# rako-bridge.net
KiCad netlist of a schematic drawn in EAGLE
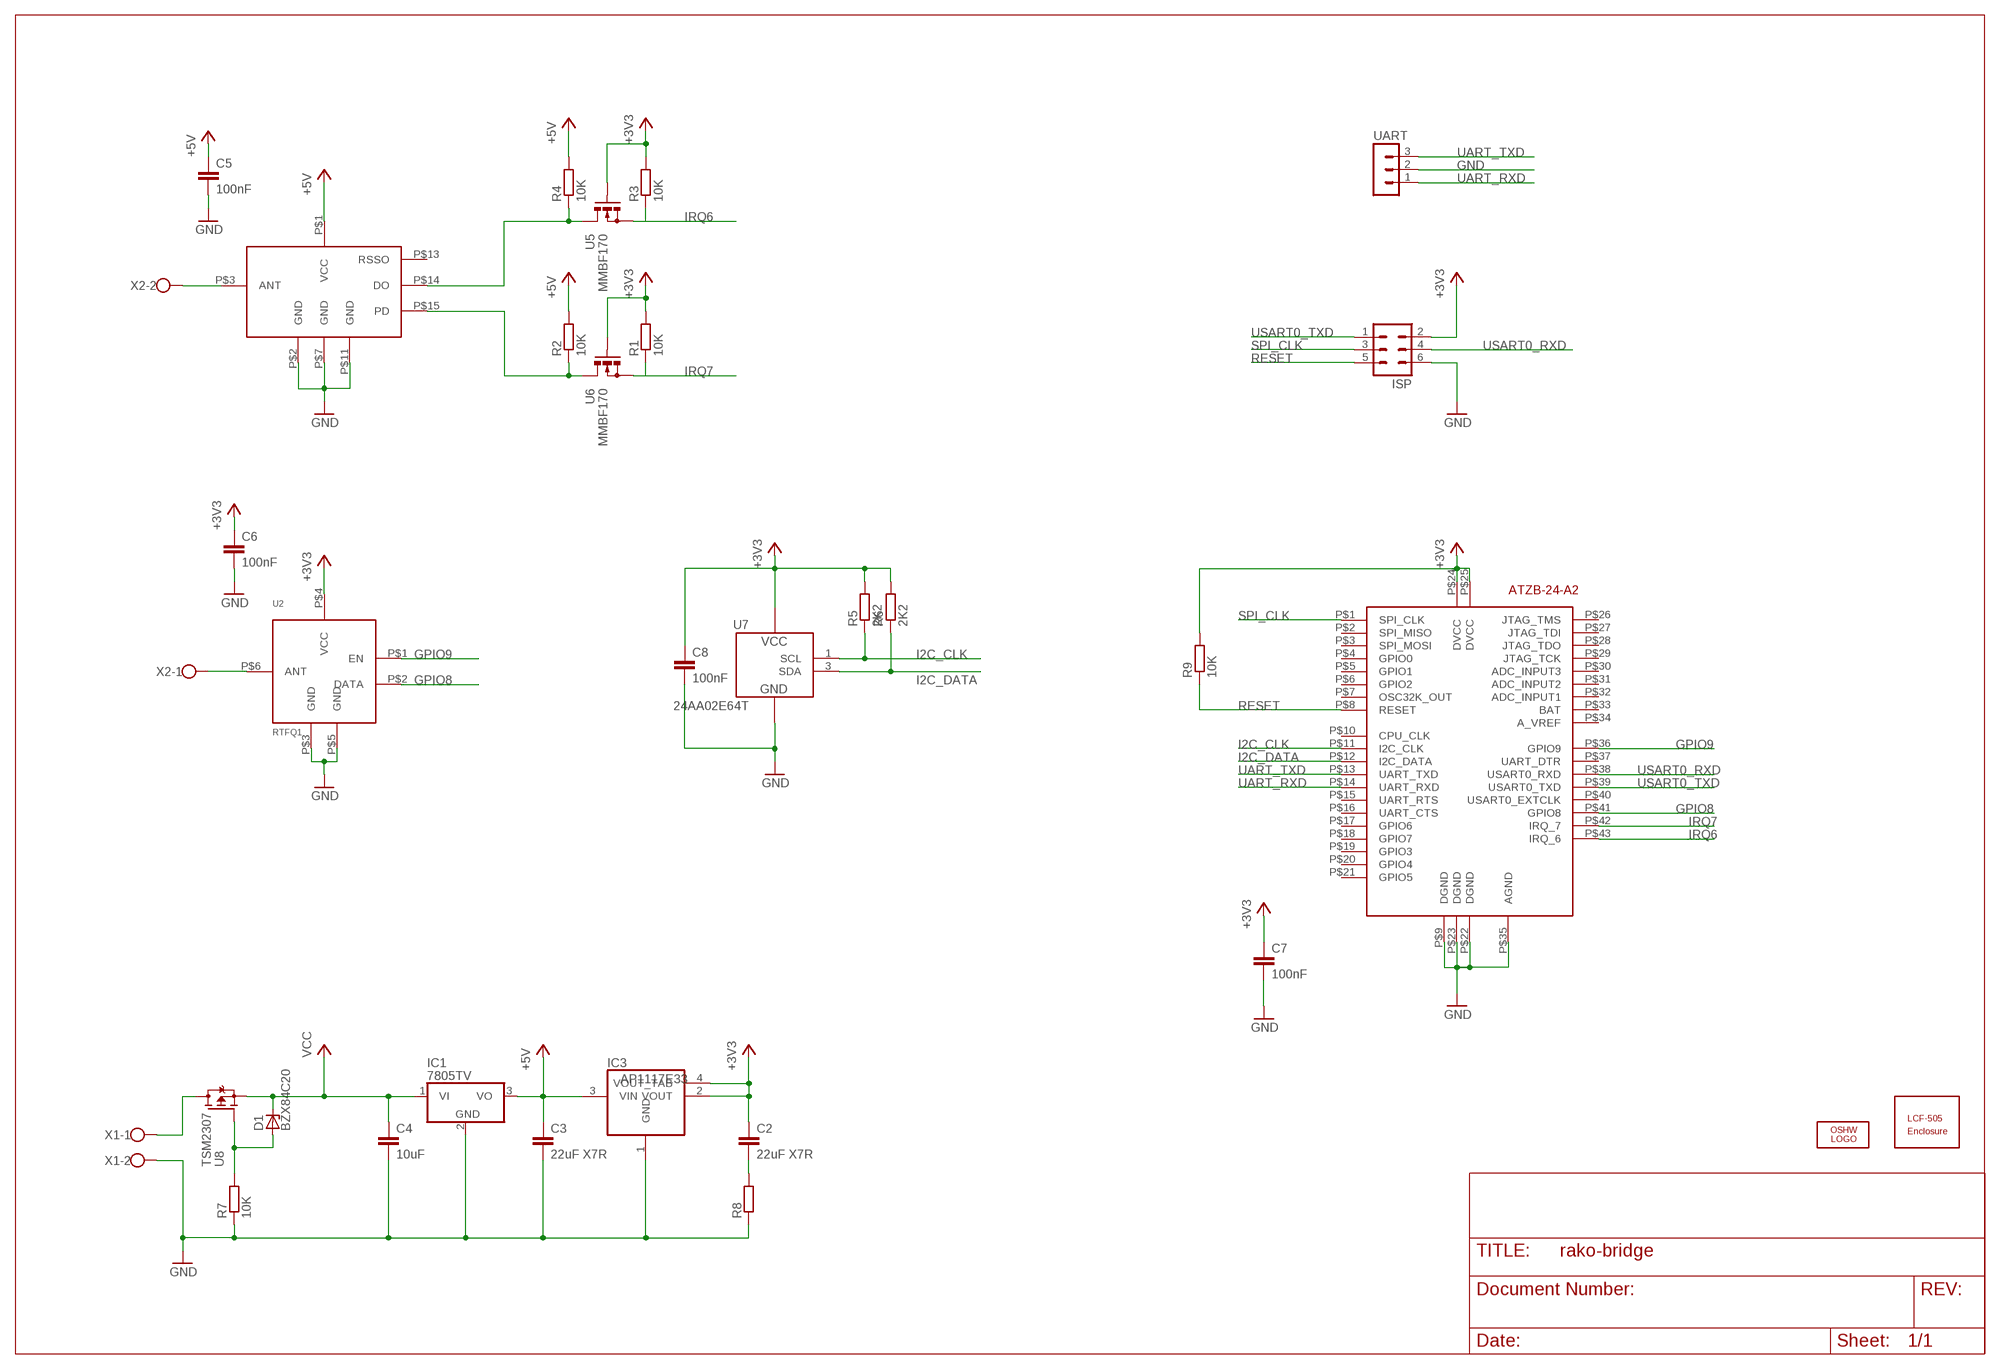
[diagram p0: schematic, sheet 1]

(export (version "E")
  (design (tool "Eeschema 10.0.6"))
  (components
    (comp (ref "C2")
      (value "22uF X7R")
      (footprint "eagle-import:C1210")
      (libsource (lib "eagle-import") (part "C-EUC1210"))
    )
    (comp (ref "C3")
      (value "22uF X7R")
      (footprint "eagle-import:C1210")
      (libsource (lib "eagle-import") (part "C-EUC1210"))
    )
    (comp (ref "C4")
      (value "10uF")
      (footprint "eagle-import:C1210")
      (libsource (lib "eagle-import") (part "C-EUC1210"))
    )
    (comp (ref "C5")
      (value "100nF")
      (footprint "eagle-import:C0603")
      (libsource (lib "eagle-import") (part "C-EUC0603"))
    )
    (comp (ref "C6")
      (value "100nF")
      (footprint "eagle-import:C0603")
      (libsource (lib "eagle-import") (part "C-EUC0603"))
    )
    (comp (ref "C7")
      (value "100nF")
      (footprint "eagle-import:C0603")
      (libsource (lib "eagle-import") (part "C-EUC0603"))
    )
    (comp (ref "C8")
      (value "100nF")
      (footprint "eagle-import:C0603")
      (libsource (lib "eagle-import") (part "C-EUC0603"))
    )
    (comp (ref "D1")
      (value "BZX84C20")
      (footprint "eagle-import:SOT23")
      (libsource (lib "eagle-import") (part "BZX84C"))
    )
    (comp (ref "IC1")
      (value "7805TV")
      (footprint "eagle-import:TO220V")
      (libsource (lib "eagle-import") (part "78TV05"))
    )
    (comp (ref "IC3")
      (value "AP1117E33")
      (footprint "eagle-import:SOT223")
      (fields (field (name "MPN") "REG1117"))
      (libsource (lib "eagle-import") (part "REG1117"))
    )
    (comp (ref "ISP")
      (value "MA03-2")
      (footprint "eagle-import:MA03-2")
      (libsource (lib "eagle-import") (part "MA03-2"))
    )
    (comp (ref "LOGO1")
      (value "OSHW_LOGO_FILLX0200-NT")
      (footprint "eagle-import:OSHW_FILLX200_NOTEXT")
      (libsource (lib "eagle-import") (part "OSHW_LOGO_FILLX0200-NT"))
    )
    (comp (ref "R1")
      (value "10K")
      (footprint "eagle-import:R0603")
      (libsource (lib "eagle-import") (part "R-EU_R0603"))
    )
    (comp (ref "R2")
      (value "10K")
      (footprint "eagle-import:R0603")
      (libsource (lib "eagle-import") (part "R-EU_R0603"))
    )
    (comp (ref "R3")
      (value "10K")
      (footprint "eagle-import:R0603")
      (libsource (lib "eagle-import") (part "R-EU_R0603"))
    )
    (comp (ref "R4")
      (value "10K")
      (footprint "eagle-import:R0603")
      (libsource (lib "eagle-import") (part "R-EU_R0603"))
    )
    (comp (ref "R5")
      (value "2K2")
      (footprint "eagle-import:R0603")
      (libsource (lib "eagle-import") (part "R-EU_R0603"))
    )
    (comp (ref "R6")
      (value "2K2")
      (footprint "eagle-import:R0603")
      (libsource (lib "eagle-import") (part "R-EU_R0603"))
    )
    (comp (ref "R7")
      (value "10K")
      (footprint "eagle-import:R0603")
      (libsource (lib "eagle-import") (part "R-EU_R0603"))
    )
    (comp (ref "R8")
      (value "R-EU_R0603")
      (footprint "eagle-import:R0603")
      (libsource (lib "eagle-import") (part "R-EU_R0603"))
    )
    (comp (ref "R9")
      (value "10K")
      (footprint "eagle-import:R0603")
      (libsource (lib "eagle-import") (part "R-EU_R0603"))
    )
    (comp (ref "U$1")
      (value "BOX-LCF-505")
      (footprint "eagle-import:BOX-LCF-505")
      (libsource (lib "eagle-import") (part "BOX-LCF-505"))
    )
    (comp (ref "U$3")
      (value "ATZB-24-A2")
      (footprint "eagle-import:ATZB-24-A2")
      (libsource (lib "eagle-import") (part "ATZB-24-A2"))
    )
    (comp (ref "U2")
      (value "RTFQ1")
      (footprint "eagle-import:RTFQ1")
      (libsource (lib "eagle-import") (part "RTFQ1"))
    )
    (comp (ref "U4")
      (value "RRFQ1")
      (footprint "eagle-import:RRFQ1")
      (libsource (lib "eagle-import") (part "RRFQ1"))
    )
    (comp (ref "U5")
      (value "MMBF170")
      (footprint "eagle-import:SOT23")
      (libsource (lib "eagle-import") (part "MMBF170"))
    )
    (comp (ref "U6")
      (value "MMBF170")
      (footprint "eagle-import:SOT23")
      (libsource (lib "eagle-import") (part "MMBF170"))
    )
    (comp (ref "U7")
      (value "24AA02E64T")
      (footprint "eagle-import:SOT23-5L")
      (libsource (lib "eagle-import") (part "24AA02E64T"))
    )
    (comp (ref "U8")
      (value "TSM2307")
      (footprint "eagle-import:SOT23")
      (libsource (lib "eagle-import") (part "TSM2307"))
    )
    (comp (ref "UART")
      (value "MA03-1")
      (footprint "eagle-import:MA03-1")
      (libsource (lib "eagle-import") (part "MA03-1"))
    )
    (comp (ref "X1")
      (value "W237-102")
      (footprint "eagle-import:W237-102")
      (fields (field (name "MPN") "237-102"))
      (libsource (lib "eagle-import") (part "W237-102"))
    )
    (comp (ref "X2")
      (value "W237-102")
      (footprint "eagle-import:W237-102")
      (fields (field (name "MPN") "237-102"))
      (libsource (lib "eagle-import") (part "W237-102"))
    )
  )
  (nets
    (net (code "1") (name "+3V3") (class "Default")
      (node (ref "C2") (pin "1") (pinfunction "1_1") (pintype "passive"))
      (node (ref "C6") (pin "1") (pinfunction "1_1") (pintype "passive"))
      (node (ref "C7") (pin "1") (pinfunction "1_1") (pintype "passive"))
      (node (ref "C8") (pin "1") (pinfunction "1_1") (pintype "passive"))
      (node (ref "IC3") (pin "2") (pinfunction "VOUT_2") (pintype "output"))
      (node (ref "IC3") (pin "4") (pinfunction "VOUT_TAB_4") (pintype "output"))
      (node (ref "ISP") (pin "2") (pinfunction "2_2") (pintype "passive"))
      (node (ref "R1") (pin "2") (pinfunction "2_2") (pintype "passive"))
      (node (ref "R3") (pin "2") (pinfunction "2_2") (pintype "passive"))
      (node (ref "R5") (pin "2") (pinfunction "2_2") (pintype "passive"))
      (node (ref "R6") (pin "2") (pinfunction "2_2") (pintype "passive"))
      (node (ref "R9") (pin "2") (pinfunction "2_2") (pintype "passive"))
      (node (ref "U$3") (pin "P$24") (pinfunction "DVCC_P$24") (pintype "bidirectional"))
      (node (ref "U$3") (pin "P$25") (pinfunction "DVCC_P$25") (pintype "bidirectional"))
      (node (ref "U2") (pin "P$4") (pinfunction "VCC_P$4") (pintype "bidirectional"))
      (node (ref "U5") (pin "1") (pinfunction "G_1") (pintype "passive"))
      (node (ref "U6") (pin "1") (pinfunction "G_1") (pintype "passive"))
      (node (ref "U7") (pin "4") (pinfunction "VCC_4") (pintype "bidirectional"))
    )
    (net (code "2") (name "+5V") (class "Default")
      (node (ref "C3") (pin "1") (pinfunction "1_1") (pintype "passive"))
      (node (ref "C5") (pin "1") (pinfunction "1_1") (pintype "passive"))
      (node (ref "IC1") (pin "3") (pinfunction "VO_3") (pintype "passive"))
      (node (ref "IC3") (pin "3") (pinfunction "VIN_3") (pintype "input"))
      (node (ref "R2") (pin "2") (pinfunction "2_2") (pintype "passive"))
      (node (ref "R4") (pin "2") (pinfunction "2_2") (pintype "passive"))
      (node (ref "U4") (pin "P$1") (pinfunction "VCC_P$1") (pintype "bidirectional"))
    )
    (net (code "3") (name "/GPIO8") (class "Default")
      (node (ref "U$3") (pin "P$41") (pinfunction "GPIO8_P$41") (pintype "bidirectional"))
      (node (ref "U2") (pin "P$2") (pinfunction "DATA_P$2") (pintype "bidirectional"))
    )
    (net (code "4") (name "/GPIO9") (class "Default")
      (node (ref "U$3") (pin "P$36") (pinfunction "GPIO9_P$36") (pintype "bidirectional"))
      (node (ref "U2") (pin "P$1") (pinfunction "EN_P$1") (pintype "bidirectional"))
    )
    (net (code "5") (name "/I2C_CLK") (class "Default")
      (node (ref "R5") (pin "1") (pinfunction "1_1") (pintype "passive"))
      (node (ref "U$3") (pin "P$11") (pinfunction "I2C_CLK_P$11") (pintype "bidirectional"))
      (node (ref "U7") (pin "1") (pinfunction "SCL_1") (pintype "bidirectional"))
    )
    (net (code "6") (name "/I2C_DATA") (class "Default")
      (node (ref "R6") (pin "1") (pinfunction "1_1") (pintype "passive"))
      (node (ref "U$3") (pin "P$12") (pinfunction "I2C_DATA_P$12") (pintype "bidirectional"))
      (node (ref "U7") (pin "3") (pinfunction "SDA_3") (pintype "bidirectional"))
    )
    (net (code "7") (name "/IRQ6") (class "Default")
      (node (ref "R3") (pin "1") (pinfunction "1_1") (pintype "passive"))
      (node (ref "U$3") (pin "P$43") (pinfunction "IRQ_6_P$43") (pintype "bidirectional"))
      (node (ref "U5") (pin "2") (pinfunction "S_2") (pintype "passive"))
    )
    (net (code "8") (name "/IRQ7") (class "Default")
      (node (ref "R1") (pin "1") (pinfunction "1_1") (pintype "passive"))
      (node (ref "U$3") (pin "P$42") (pinfunction "IRQ_7_P$42") (pintype "bidirectional"))
      (node (ref "U6") (pin "2") (pinfunction "S_2") (pintype "passive"))
    )
    (net (code "9") (name "/RESET") (class "Default")
      (node (ref "ISP") (pin "5") (pinfunction "5_5") (pintype "passive"))
      (node (ref "R9") (pin "1") (pinfunction "1_1") (pintype "passive"))
      (node (ref "U$3") (pin "P$8") (pinfunction "RESET_P$8") (pintype "bidirectional"))
    )
    (net (code "10") (name "/SPI_CLK") (class "Default")
      (node (ref "ISP") (pin "3") (pinfunction "3_3") (pintype "passive"))
      (node (ref "U$3") (pin "P$1") (pinfunction "SPI_CLK_P$1") (pintype "bidirectional"))
    )
    (net (code "11") (name "/UART_RXD") (class "Default")
      (node (ref "U$3") (pin "P$14") (pinfunction "UART_RXD_P$14") (pintype "bidirectional"))
      (node (ref "UART") (pin "1") (pinfunction "1_1") (pintype "passive"))
    )
    (net (code "12") (name "/UART_TXD") (class "Default")
      (node (ref "U$3") (pin "P$13") (pinfunction "UART_TXD_P$13") (pintype "bidirectional"))
      (node (ref "UART") (pin "3") (pinfunction "3_3") (pintype "passive"))
    )
    (net (code "13") (name "/USART0_RXD") (class "Default")
      (node (ref "ISP") (pin "4") (pinfunction "4_4") (pintype "passive"))
      (node (ref "U$3") (pin "P$38") (pinfunction "USART0_RXD_P$38") (pintype "bidirectional"))
    )
    (net (code "14") (name "/USART0_TXD") (class "Default")
      (node (ref "ISP") (pin "1") (pinfunction "1_1") (pintype "passive"))
      (node (ref "U$3") (pin "P$39") (pinfunction "USART0_TXD_P$39") (pintype "bidirectional"))
    )
    (net (code "15") (name "GND") (class "Default")
      (node (ref "C3") (pin "2") (pinfunction "2_2") (pintype "passive"))
      (node (ref "C4") (pin "2") (pinfunction "2_2") (pintype "passive"))
      (node (ref "C5") (pin "2") (pinfunction "2_2") (pintype "passive"))
      (node (ref "C6") (pin "2") (pinfunction "2_2") (pintype "passive"))
      (node (ref "C7") (pin "2") (pinfunction "2_2") (pintype "passive"))
      (node (ref "C8") (pin "2") (pinfunction "2_2") (pintype "passive"))
      (node (ref "IC1") (pin "2") (pinfunction "GND_2") (pintype "passive"))
      (node (ref "IC3") (pin "1") (pinfunction "GND_1") (pintype "power_in"))
      (node (ref "ISP") (pin "6") (pinfunction "6_6") (pintype "passive"))
      (node (ref "R7") (pin "1") (pinfunction "1_1") (pintype "passive"))
      (node (ref "R8") (pin "1") (pinfunction "1_1") (pintype "passive"))
      (node (ref "U$3") (pin "P$22") (pinfunction "DGND_P$22") (pintype "bidirectional"))
      (node (ref "U$3") (pin "P$23") (pinfunction "DGND_P$23") (pintype "bidirectional"))
      (node (ref "U$3") (pin "P$35") (pinfunction "AGND_P$35") (pintype "bidirectional"))
      (node (ref "U$3") (pin "P$9") (pinfunction "DGND_P$9") (pintype "bidirectional"))
      (node (ref "U2") (pin "P$3") (pinfunction "GND_P$3") (pintype "bidirectional"))
      (node (ref "U2") (pin "P$5") (pinfunction "GND_P$5") (pintype "bidirectional"))
      (node (ref "U4") (pin "P$11") (pinfunction "GND_P$11") (pintype "bidirectional"))
      (node (ref "U4") (pin "P$2") (pinfunction "GND_P$2") (pintype "bidirectional"))
      (node (ref "U4") (pin "P$7") (pinfunction "GND_P$7") (pintype "bidirectional"))
      (node (ref "U7") (pin "2") (pinfunction "VSS_2") (pintype "bidirectional"))
      (node (ref "UART") (pin "2") (pinfunction "2_2") (pintype "passive"))
      (node (ref "X1") (pin "2") (pinfunction "KL_2") (pintype "passive"))
    )
    (net (code "16") (name "Net-(C2-Pad2)") (class "Default")
      (node (ref "C2") (pin "2") (pinfunction "2_2") (pintype "passive"))
      (node (ref "R8") (pin "2") (pinfunction "2_2") (pintype "passive"))
    )
    (net (code "17") (name "Net-(D1-A)") (class "Default")
      (node (ref "D1") (pin "1") (pinfunction "A_1") (pintype "passive"))
      (node (ref "R7") (pin "2") (pinfunction "2_2") (pintype "passive"))
      (node (ref "U8") (pin "1") (pinfunction "G_1") (pintype "passive"))
    )
    (net (code "18") (name "Net-(U2-ANT)") (class "Default")
      (node (ref "U2") (pin "P$6") (pinfunction "ANT_P$6") (pintype "bidirectional"))
      (node (ref "X2") (pin "1") (pinfunction "KL_1") (pintype "passive"))
    )
    (net (code "19") (name "Net-(U4-ANT)") (class "Default")
      (node (ref "U4") (pin "P$3") (pinfunction "ANT_P$3") (pintype "bidirectional"))
      (node (ref "X2") (pin "2") (pinfunction "KL_2") (pintype "passive"))
    )
    (net (code "20") (name "Net-(U4-DO)") (class "Default")
      (node (ref "R4") (pin "1") (pinfunction "1_1") (pintype "passive"))
      (node (ref "U4") (pin "P$14") (pinfunction "DO_P$14") (pintype "bidirectional"))
      (node (ref "U5") (pin "3") (pinfunction "D_3") (pintype "passive"))
    )
    (net (code "21") (name "Net-(U4-PD)") (class "Default")
      (node (ref "R2") (pin "1") (pinfunction "1_1") (pintype "passive"))
      (node (ref "U4") (pin "P$15") (pinfunction "PD_P$15") (pintype "bidirectional"))
      (node (ref "U6") (pin "3") (pinfunction "D_3") (pintype "passive"))
    )
    (net (code "22") (name "Net-(U8-D)") (class "Default")
      (node (ref "U8") (pin "3") (pinfunction "D_3") (pintype "passive"))
      (node (ref "X1") (pin "1") (pinfunction "KL_1") (pintype "passive"))
    )
    (net (code "23") (name "VCC") (class "Default")
      (node (ref "C4") (pin "1") (pinfunction "1_1") (pintype "passive"))
      (node (ref "D1") (pin "3") (pinfunction "C_3") (pintype "passive"))
      (node (ref "IC1") (pin "1") (pinfunction "VI_1") (pintype "input"))
      (node (ref "U8") (pin "2") (pinfunction "S_2") (pintype "passive"))
    )
    (net (code "24") (name "unconnected-(U$3-ADC_INPUT1-PadP$32)") (class "Default")
      (node (ref "U$3") (pin "P$32") (pinfunction "ADC_INPUT1_P$32") (pintype "bidirectional"))
    )
    (net (code "25") (name "unconnected-(U$3-ADC_INPUT2-PadP$31)") (class "Default")
      (node (ref "U$3") (pin "P$31") (pinfunction "ADC_INPUT2_P$31") (pintype "bidirectional"))
    )
    (net (code "26") (name "unconnected-(U$3-ADC_INPUT3-PadP$30)") (class "Default")
      (node (ref "U$3") (pin "P$30") (pinfunction "ADC_INPUT3_P$30") (pintype "bidirectional"))
    )
    (net (code "27") (name "unconnected-(U$3-A_VREF-PadP$34)") (class "Default")
      (node (ref "U$3") (pin "P$34") (pinfunction "A_VREF_P$34") (pintype "bidirectional"))
    )
    (net (code "28") (name "unconnected-(U$3-BAT-PadP$33)") (class "Default")
      (node (ref "U$3") (pin "P$33") (pinfunction "BAT_P$33") (pintype "bidirectional"))
    )
    (net (code "29") (name "unconnected-(U$3-CPU_CLK-PadP$10)") (class "Default")
      (node (ref "U$3") (pin "P$10") (pinfunction "CPU_CLK_P$10") (pintype "bidirectional"))
    )
    (net (code "30") (name "unconnected-(U$3-GPIO0-PadP$4)") (class "Default")
      (node (ref "U$3") (pin "P$4") (pinfunction "GPIO0_P$4") (pintype "bidirectional"))
    )
    (net (code "31") (name "unconnected-(U$3-GPIO1-PadP$5)") (class "Default")
      (node (ref "U$3") (pin "P$5") (pinfunction "GPIO1_P$5") (pintype "bidirectional"))
    )
    (net (code "32") (name "unconnected-(U$3-GPIO2-PadP$6)") (class "Default")
      (node (ref "U$3") (pin "P$6") (pinfunction "GPIO2_P$6") (pintype "bidirectional"))
    )
    (net (code "33") (name "unconnected-(U$3-GPIO3-PadP$19)") (class "Default")
      (node (ref "U$3") (pin "P$19") (pinfunction "GPIO3_P$19") (pintype "bidirectional"))
    )
    (net (code "34") (name "unconnected-(U$3-GPIO4-PadP$20)") (class "Default")
      (node (ref "U$3") (pin "P$20") (pinfunction "GPIO4_P$20") (pintype "bidirectional"))
    )
    (net (code "35") (name "unconnected-(U$3-GPIO5-PadP$21)") (class "Default")
      (node (ref "U$3") (pin "P$21") (pinfunction "GPIO5_P$21") (pintype "bidirectional"))
    )
    (net (code "36") (name "unconnected-(U$3-GPIO6-PadP$17)") (class "Default")
      (node (ref "U$3") (pin "P$17") (pinfunction "GPIO6_P$17") (pintype "bidirectional"))
    )
    (net (code "37") (name "unconnected-(U$3-GPIO7-PadP$18)") (class "Default")
      (node (ref "U$3") (pin "P$18") (pinfunction "GPIO7_P$18") (pintype "bidirectional"))
    )
    (net (code "38") (name "unconnected-(U$3-JTAG_TCK-PadP$29)") (class "Default")
      (node (ref "U$3") (pin "P$29") (pinfunction "JTAG_TCK_P$29") (pintype "bidirectional"))
    )
    (net (code "39") (name "unconnected-(U$3-JTAG_TDI-PadP$27)") (class "Default")
      (node (ref "U$3") (pin "P$27") (pinfunction "JTAG_TDI_P$27") (pintype "bidirectional"))
    )
    (net (code "40") (name "unconnected-(U$3-JTAG_TDO-PadP$28)") (class "Default")
      (node (ref "U$3") (pin "P$28") (pinfunction "JTAG_TDO_P$28") (pintype "bidirectional"))
    )
    (net (code "41") (name "unconnected-(U$3-JTAG_TMS-PadP$26)") (class "Default")
      (node (ref "U$3") (pin "P$26") (pinfunction "JTAG_TMS_P$26") (pintype "bidirectional"))
    )
    (net (code "42") (name "unconnected-(U$3-OSC32K_OUT-PadP$7)") (class "Default")
      (node (ref "U$3") (pin "P$7") (pinfunction "OSC32K_OUT_P$7") (pintype "bidirectional"))
    )
    (net (code "43") (name "unconnected-(U$3-SPI_MISO-PadP$2)") (class "Default")
      (node (ref "U$3") (pin "P$2") (pinfunction "SPI_MISO_P$2") (pintype "bidirectional"))
    )
    (net (code "44") (name "unconnected-(U$3-SPI_MOSI-PadP$3)") (class "Default")
      (node (ref "U$3") (pin "P$3") (pinfunction "SPI_MOSI_P$3") (pintype "bidirectional"))
    )
    (net (code "45") (name "unconnected-(U$3-UART_CTS-PadP$16)") (class "Default")
      (node (ref "U$3") (pin "P$16") (pinfunction "UART_CTS_P$16") (pintype "bidirectional"))
    )
    (net (code "46") (name "unconnected-(U$3-UART_DTR-PadP$37)") (class "Default")
      (node (ref "U$3") (pin "P$37") (pinfunction "UART_DTR_P$37") (pintype "bidirectional"))
    )
    (net (code "47") (name "unconnected-(U$3-UART_RTS-PadP$15)") (class "Default")
      (node (ref "U$3") (pin "P$15") (pinfunction "UART_RTS_P$15") (pintype "bidirectional"))
    )
    (net (code "48") (name "unconnected-(U$3-USART0_EXTCLK-PadP$40)") (class "Default")
      (node (ref "U$3") (pin "P$40") (pinfunction "USART0_EXTCLK_P$40") (pintype "bidirectional"))
    )
    (net (code "49") (name "unconnected-(U4-RSSO-PadP$13)") (class "Default")
      (node (ref "U4") (pin "P$13") (pinfunction "RSSO_P$13") (pintype "bidirectional"))
    )
  )
)
